# HMI_Buttons.net
KiCad netlist of a schematic drawn in Altium Designer
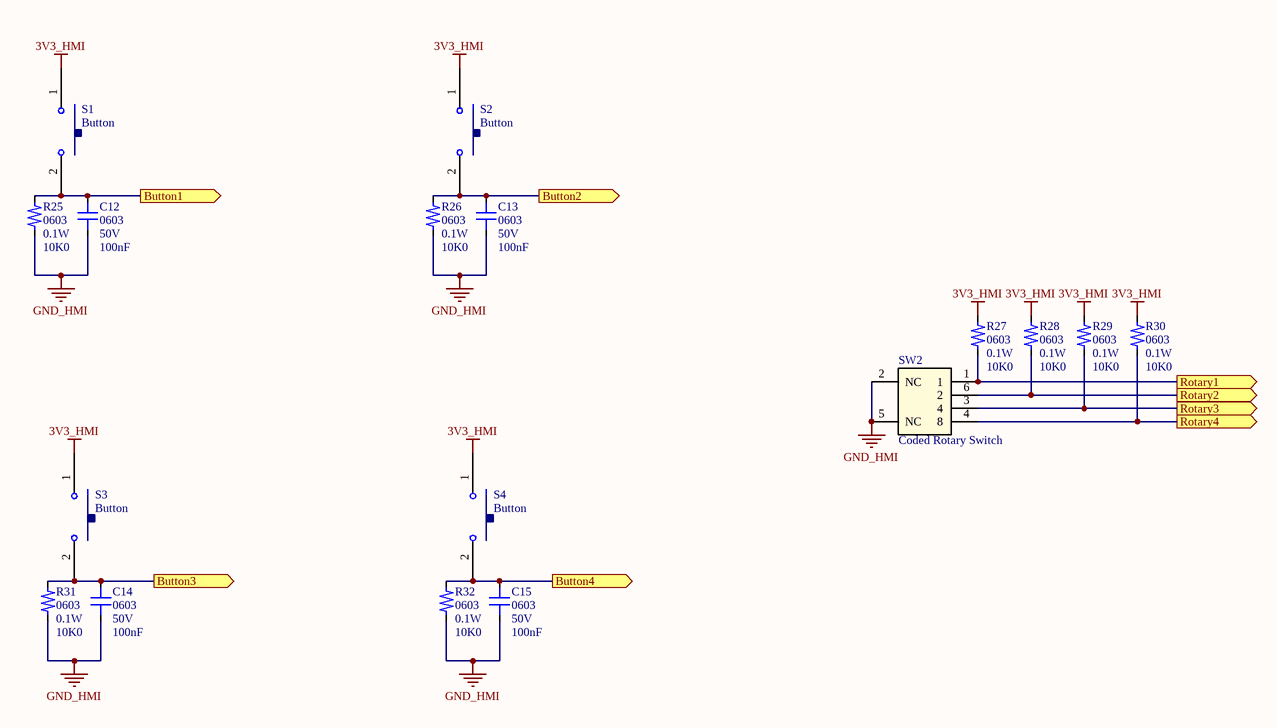
[diagram p0: HMI_Buttons.SchDoc]

(export (version "E")
  (design (tool "Eeschema 10.0.6"))
  (components
    (comp (ref "C12")
      (value "0603")
      (footprint "C_0603")
      (fields
        (field (name "TOLERANCE") "10%")
        (field (name "PART NUMBER") "CC0603KRX7R9BB104")
        (field (name "RATING") "50V")
        (field (name "ALTIUM_VALUE") "100nF")
        (field (name "NI PART NUMBER") "716340-01")
      )
      (libsource (lib "Components") (part "Capacitor_Chip"))
    )
    (comp (ref "C13")
      (value "0603")
      (footprint "C_0603")
      (fields
        (field (name "TOLERANCE") "10%")
        (field (name "PART NUMBER") "CC0603KRX7R9BB104")
        (field (name "RATING") "50V")
        (field (name "ALTIUM_VALUE") "100nF")
        (field (name "NI PART NUMBER") "716340-01")
      )
      (libsource (lib "Components") (part "Capacitor_Chip"))
    )
    (comp (ref "C14")
      (value "0603")
      (footprint "C_0603")
      (fields
        (field (name "TOLERANCE") "10%")
        (field (name "PART NUMBER") "CC0603KRX7R9BB104")
        (field (name "RATING") "50V")
        (field (name "ALTIUM_VALUE") "100nF")
        (field (name "NI PART NUMBER") "716340-01")
      )
      (libsource (lib "Components") (part "Capacitor_Chip"))
    )
    (comp (ref "C15")
      (value "0603")
      (footprint "C_0603")
      (fields
        (field (name "TOLERANCE") "10%")
        (field (name "PART NUMBER") "CC0603KRX7R9BB104")
        (field (name "RATING") "50V")
        (field (name "ALTIUM_VALUE") "100nF")
        (field (name "NI PART NUMBER") "716340-01")
      )
      (libsource (lib "Components") (part "Capacitor_Chip"))
    )
    (comp (ref "R25")
      (value "0603")
      (footprint "R_0603")
      (fields
        (field (name "TOLERANCE") "1%")
        (field (name "PART NUMBER") "CR-03FL7---10K")
        (field (name "RATING") "0.1W")
        (field (name "ALTIUM_VALUE") "10K0")
        (field (name "NI PART NUMBER") "713771-01")
      )
      (libsource (lib "Components") (part "Resistor_Chip"))
    )
    (comp (ref "R26")
      (value "0603")
      (footprint "R_0603")
      (fields
        (field (name "TOLERANCE") "1%")
        (field (name "PART NUMBER") "CR-03FL7---10K")
        (field (name "RATING") "0.1W")
        (field (name "ALTIUM_VALUE") "10K0")
        (field (name "NI PART NUMBER") "713771-01")
      )
      (libsource (lib "Components") (part "Resistor_Chip"))
    )
    (comp (ref "R27")
      (value "0603")
      (footprint "R_0603")
      (fields
        (field (name "TOLERANCE") "1%")
        (field (name "PART NUMBER") "CR-03FL7---10K")
        (field (name "RATING") "0.1W")
        (field (name "ALTIUM_VALUE") "10K0")
        (field (name "NI PART NUMBER") "713771-01")
      )
      (libsource (lib "Components") (part "Resistor_Chip"))
    )
    (comp (ref "R28")
      (value "0603")
      (footprint "R_0603")
      (fields
        (field (name "TOLERANCE") "1%")
        (field (name "PART NUMBER") "CR-03FL7---10K")
        (field (name "RATING") "0.1W")
        (field (name "ALTIUM_VALUE") "10K0")
        (field (name "NI PART NUMBER") "713771-01")
      )
      (libsource (lib "Components") (part "Resistor_Chip"))
    )
    (comp (ref "R29")
      (value "0603")
      (footprint "R_0603")
      (fields
        (field (name "TOLERANCE") "1%")
        (field (name "PART NUMBER") "CR-03FL7---10K")
        (field (name "RATING") "0.1W")
        (field (name "ALTIUM_VALUE") "10K0")
        (field (name "NI PART NUMBER") "713771-01")
      )
      (libsource (lib "Components") (part "Resistor_Chip"))
    )
    (comp (ref "R30")
      (value "0603")
      (footprint "R_0603")
      (fields
        (field (name "TOLERANCE") "1%")
        (field (name "PART NUMBER") "CR-03FL7---10K")
        (field (name "RATING") "0.1W")
        (field (name "ALTIUM_VALUE") "10K0")
        (field (name "NI PART NUMBER") "713771-01")
      )
      (libsource (lib "Components") (part "Resistor_Chip"))
    )
    (comp (ref "R31")
      (value "0603")
      (footprint "R_0603")
      (fields
        (field (name "TOLERANCE") "1%")
        (field (name "PART NUMBER") "CR-03FL7---10K")
        (field (name "RATING") "0.1W")
        (field (name "ALTIUM_VALUE") "10K0")
        (field (name "NI PART NUMBER") "713771-01")
      )
      (libsource (lib "Components") (part "Resistor_Chip"))
    )
    (comp (ref "R32")
      (value "0603")
      (footprint "R_0603")
      (fields
        (field (name "TOLERANCE") "1%")
        (field (name "PART NUMBER") "CR-03FL7---10K")
        (field (name "RATING") "0.1W")
        (field (name "ALTIUM_VALUE") "10K0")
        (field (name "NI PART NUMBER") "713771-01")
      )
      (libsource (lib "Components") (part "Resistor_Chip"))
    )
    (comp (ref "S1")
      (value "Button")
      (footprint "Switch")
      (fields (field (name "PART NUMBER") "FSM2JSMA"))
      (libsource (lib "Components") (part "Button"))
    )
    (comp (ref "S2")
      (value "Button")
      (footprint "Switch")
      (fields (field (name "PART NUMBER") "FSM2JSMA"))
      (libsource (lib "Components") (part "Button"))
    )
    (comp (ref "S3")
      (value "Button")
      (footprint "Switch")
      (fields (field (name "PART NUMBER") "FSM2JSMA"))
      (libsource (lib "Components") (part "Button"))
    )
    (comp (ref "S4")
      (value "Button")
      (footprint "Switch")
      (fields (field (name "PART NUMBER") "FSM2JSMA"))
      (libsource (lib "Components") (part "Button"))
    )
    (comp (ref "SW2")
      (value "Coded Rotary Switch")
      (footprint "221AMC16R:221AMC16R")
      (libsource (lib "221AMC16R") (part "221AMC16R"))
    )
  )
  (nets
    (net (code "1") (name "/Button1") (class "Default")
      (node (ref "C12") (pin "2") (pinfunction "C2_2") (pintype "passive"))
      (node (ref "R25") (pin "2") (pinfunction "R2_2") (pintype "passive"))
      (node (ref "S1") (pin "2") (pinfunction "2_2") (pintype "passive"))
    )
    (net (code "2") (name "/Button2") (class "Default")
      (node (ref "C13") (pin "2") (pinfunction "C2_2") (pintype "passive"))
      (node (ref "R26") (pin "2") (pinfunction "R2_2") (pintype "passive"))
      (node (ref "S2") (pin "2") (pinfunction "2_2") (pintype "passive"))
    )
    (net (code "3") (name "/Button3") (class "Default")
      (node (ref "C14") (pin "2") (pinfunction "C2_2") (pintype "passive"))
      (node (ref "R31") (pin "2") (pinfunction "R2_2") (pintype "passive"))
      (node (ref "S3") (pin "2") (pinfunction "2_2") (pintype "passive"))
    )
    (net (code "4") (name "/Button4") (class "Default")
      (node (ref "C15") (pin "2") (pinfunction "C2_2") (pintype "passive"))
      (node (ref "R32") (pin "2") (pinfunction "R2_2") (pintype "passive"))
      (node (ref "S4") (pin "2") (pinfunction "2_2") (pintype "passive"))
    )
    (net (code "5") (name "/Rotary1") (class "Default")
      (node (ref "R27") (pin "1") (pinfunction "R1_1") (pintype "passive"))
      (node (ref "SW2") (pin "1") (pinfunction "1_1") (pintype "passive"))
    )
    (net (code "6") (name "/Rotary2") (class "Default")
      (node (ref "R28") (pin "1") (pinfunction "R1_1") (pintype "passive"))
      (node (ref "SW2") (pin "6") (pinfunction "2_6") (pintype "passive"))
    )
    (net (code "7") (name "/Rotary3") (class "Default")
      (node (ref "R29") (pin "1") (pinfunction "R1_1") (pintype "passive"))
      (node (ref "SW2") (pin "3") (pinfunction "4_3") (pintype "passive"))
    )
    (net (code "8") (name "/Rotary4") (class "Default")
      (node (ref "R30") (pin "1") (pinfunction "R1_1") (pintype "passive"))
      (node (ref "SW2") (pin "4") (pinfunction "8_4") (pintype "passive"))
    )
    (net (code "9") (name "3V3_HMI") (class "Default")
      (node (ref "R27") (pin "2") (pinfunction "R2_2") (pintype "passive"))
      (node (ref "R28") (pin "2") (pinfunction "R2_2") (pintype "passive"))
      (node (ref "R29") (pin "2") (pinfunction "R2_2") (pintype "passive"))
      (node (ref "R30") (pin "2") (pinfunction "R2_2") (pintype "passive"))
      (node (ref "S1") (pin "1") (pinfunction "1_1") (pintype "passive"))
      (node (ref "S2") (pin "1") (pinfunction "1_1") (pintype "passive"))
      (node (ref "S3") (pin "1") (pinfunction "1_1") (pintype "passive"))
      (node (ref "S4") (pin "1") (pinfunction "1_1") (pintype "passive"))
    )
    (net (code "10") (name "GND_HMI") (class "Default")
      (node (ref "C12") (pin "1") (pinfunction "C1_1") (pintype "passive"))
      (node (ref "C13") (pin "1") (pinfunction "C1_1") (pintype "passive"))
      (node (ref "C14") (pin "1") (pinfunction "C1_1") (pintype "passive"))
      (node (ref "C15") (pin "1") (pinfunction "C1_1") (pintype "passive"))
      (node (ref "R25") (pin "1") (pinfunction "R1_1") (pintype "passive"))
      (node (ref "R26") (pin "1") (pinfunction "R1_1") (pintype "passive"))
      (node (ref "R31") (pin "1") (pinfunction "R1_1") (pintype "passive"))
      (node (ref "R32") (pin "1") (pinfunction "R1_1") (pintype "passive"))
      (node (ref "SW2") (pin "2") (pinfunction "NC_2") (pintype "passive"))
      (node (ref "SW2") (pin "5") (pinfunction "NC_5") (pintype "passive"))
    )
  )
)
